# I2CRJ45X8.net
KiCad netlist of a schematic drawn in EAGLE
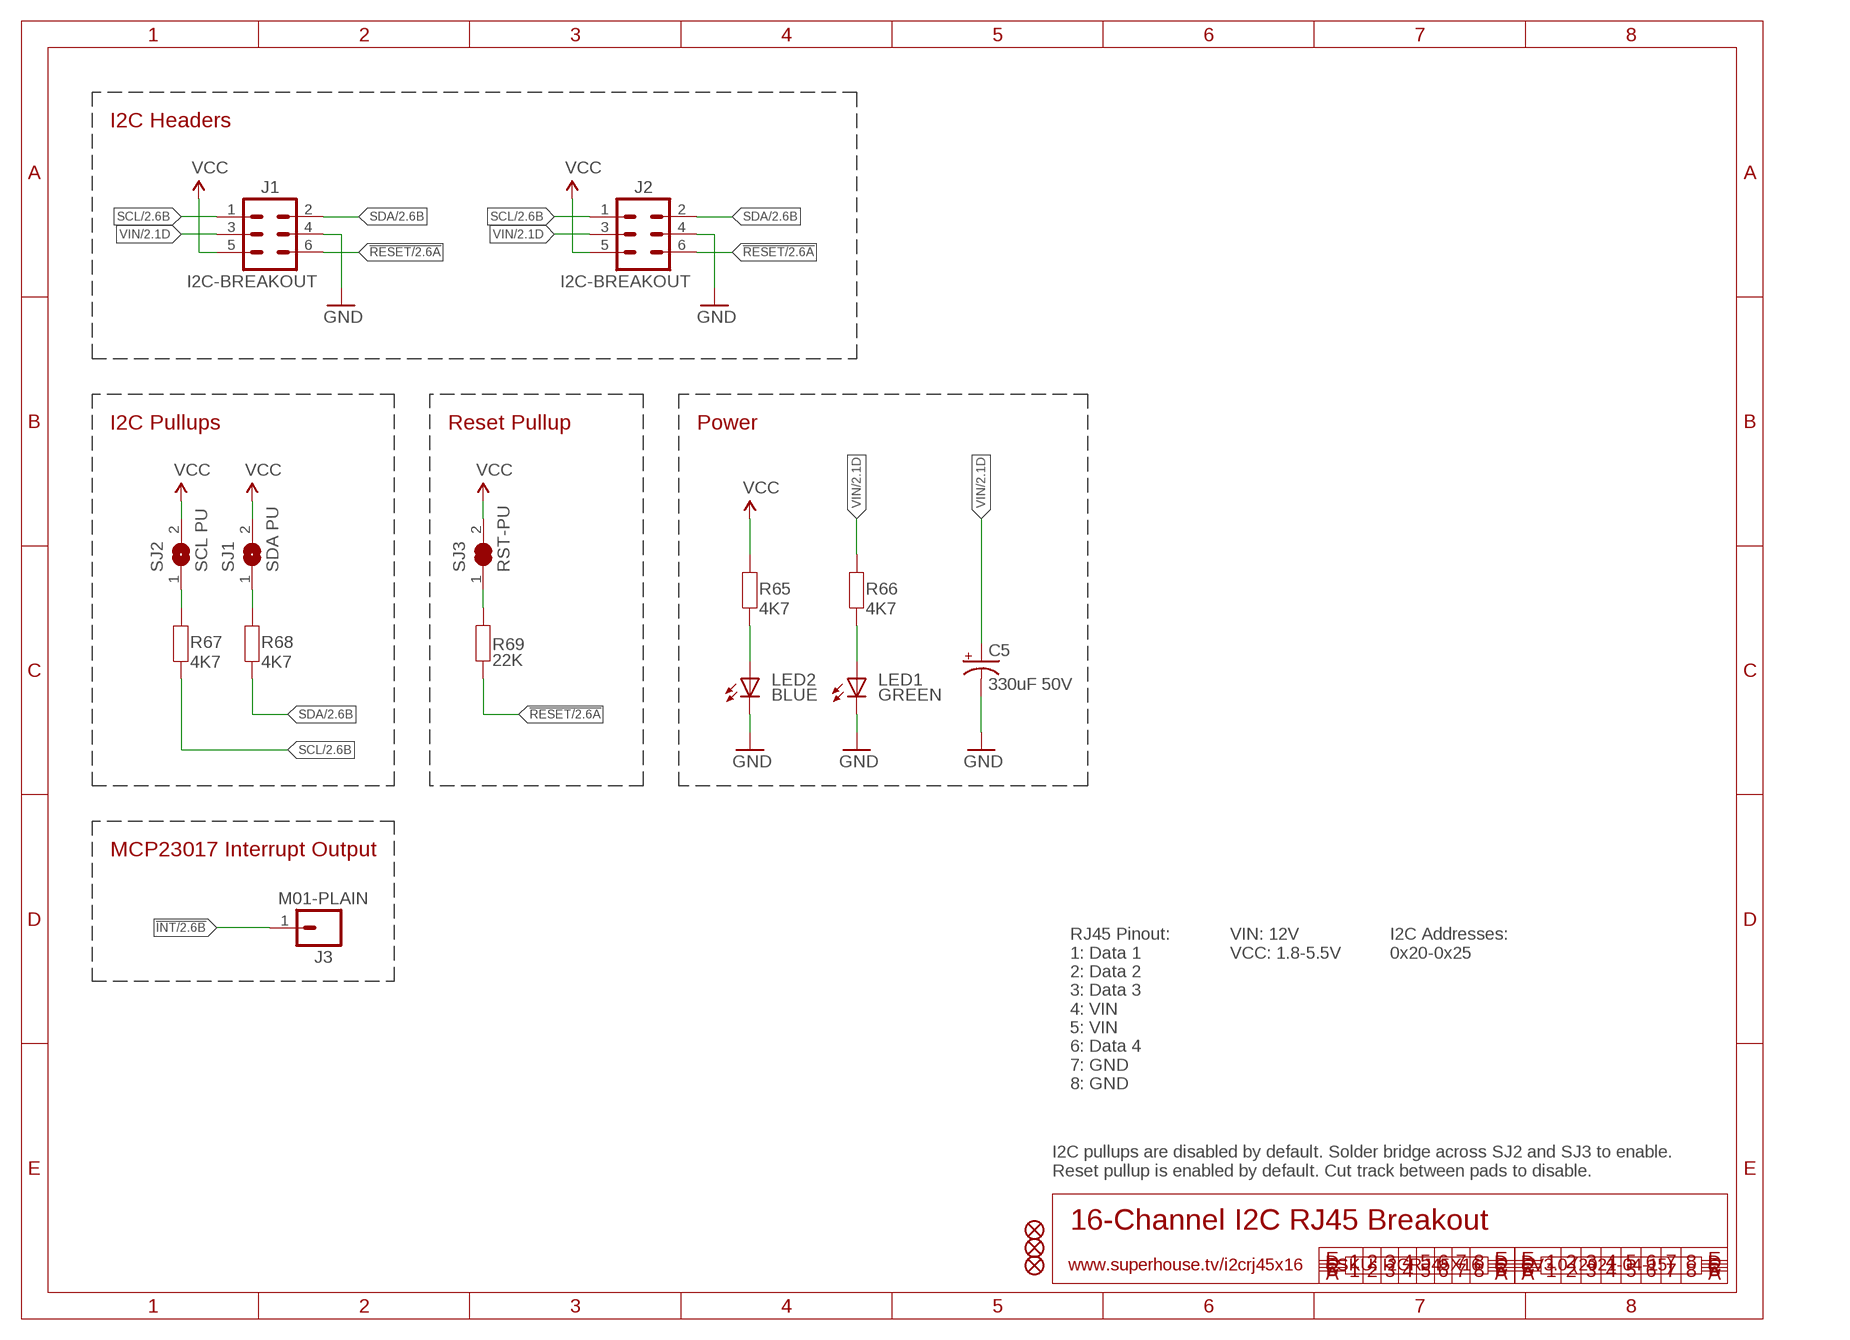
[diagram p0: schematic, sheet 1]
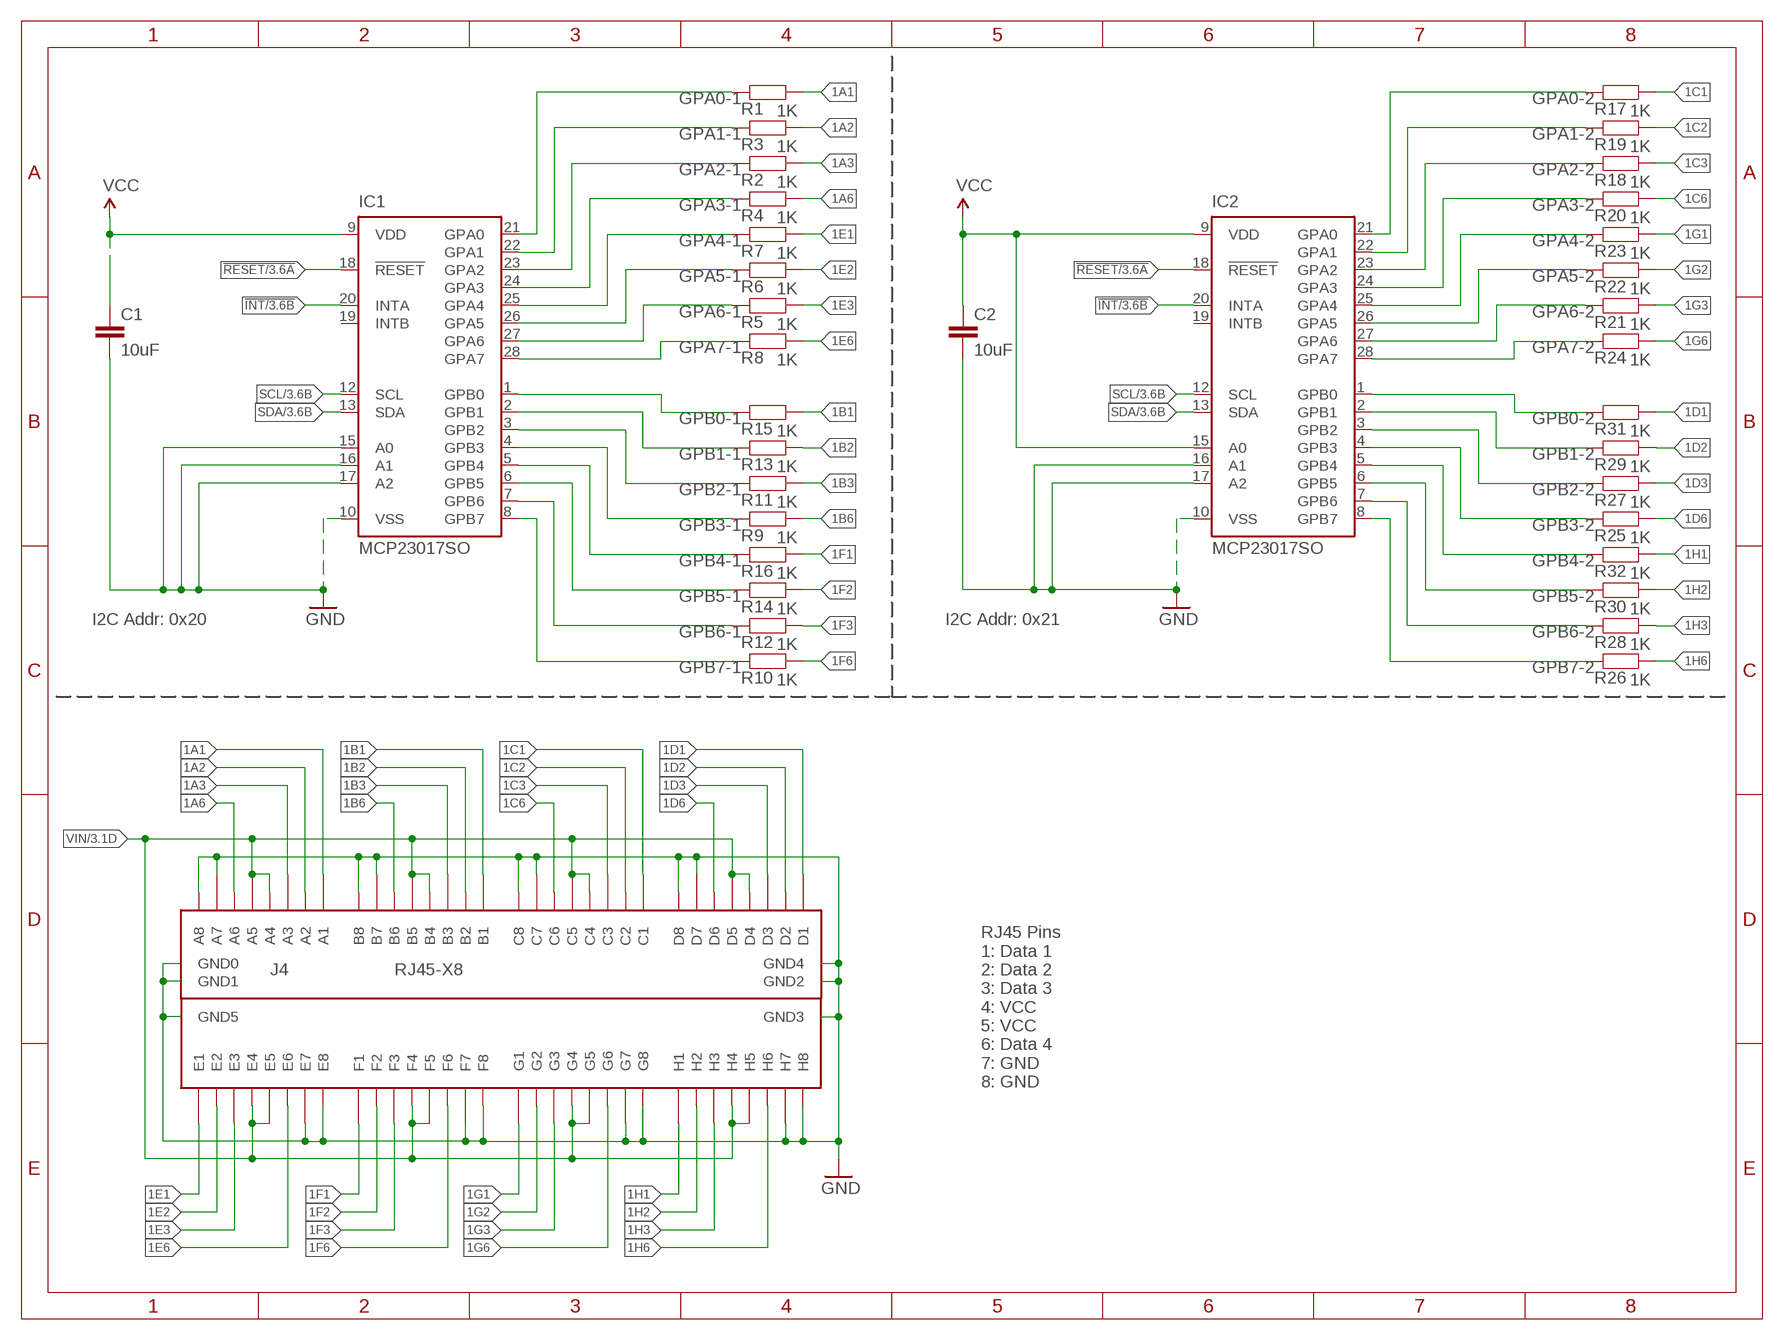
[diagram p1: schematic, sheet 2]
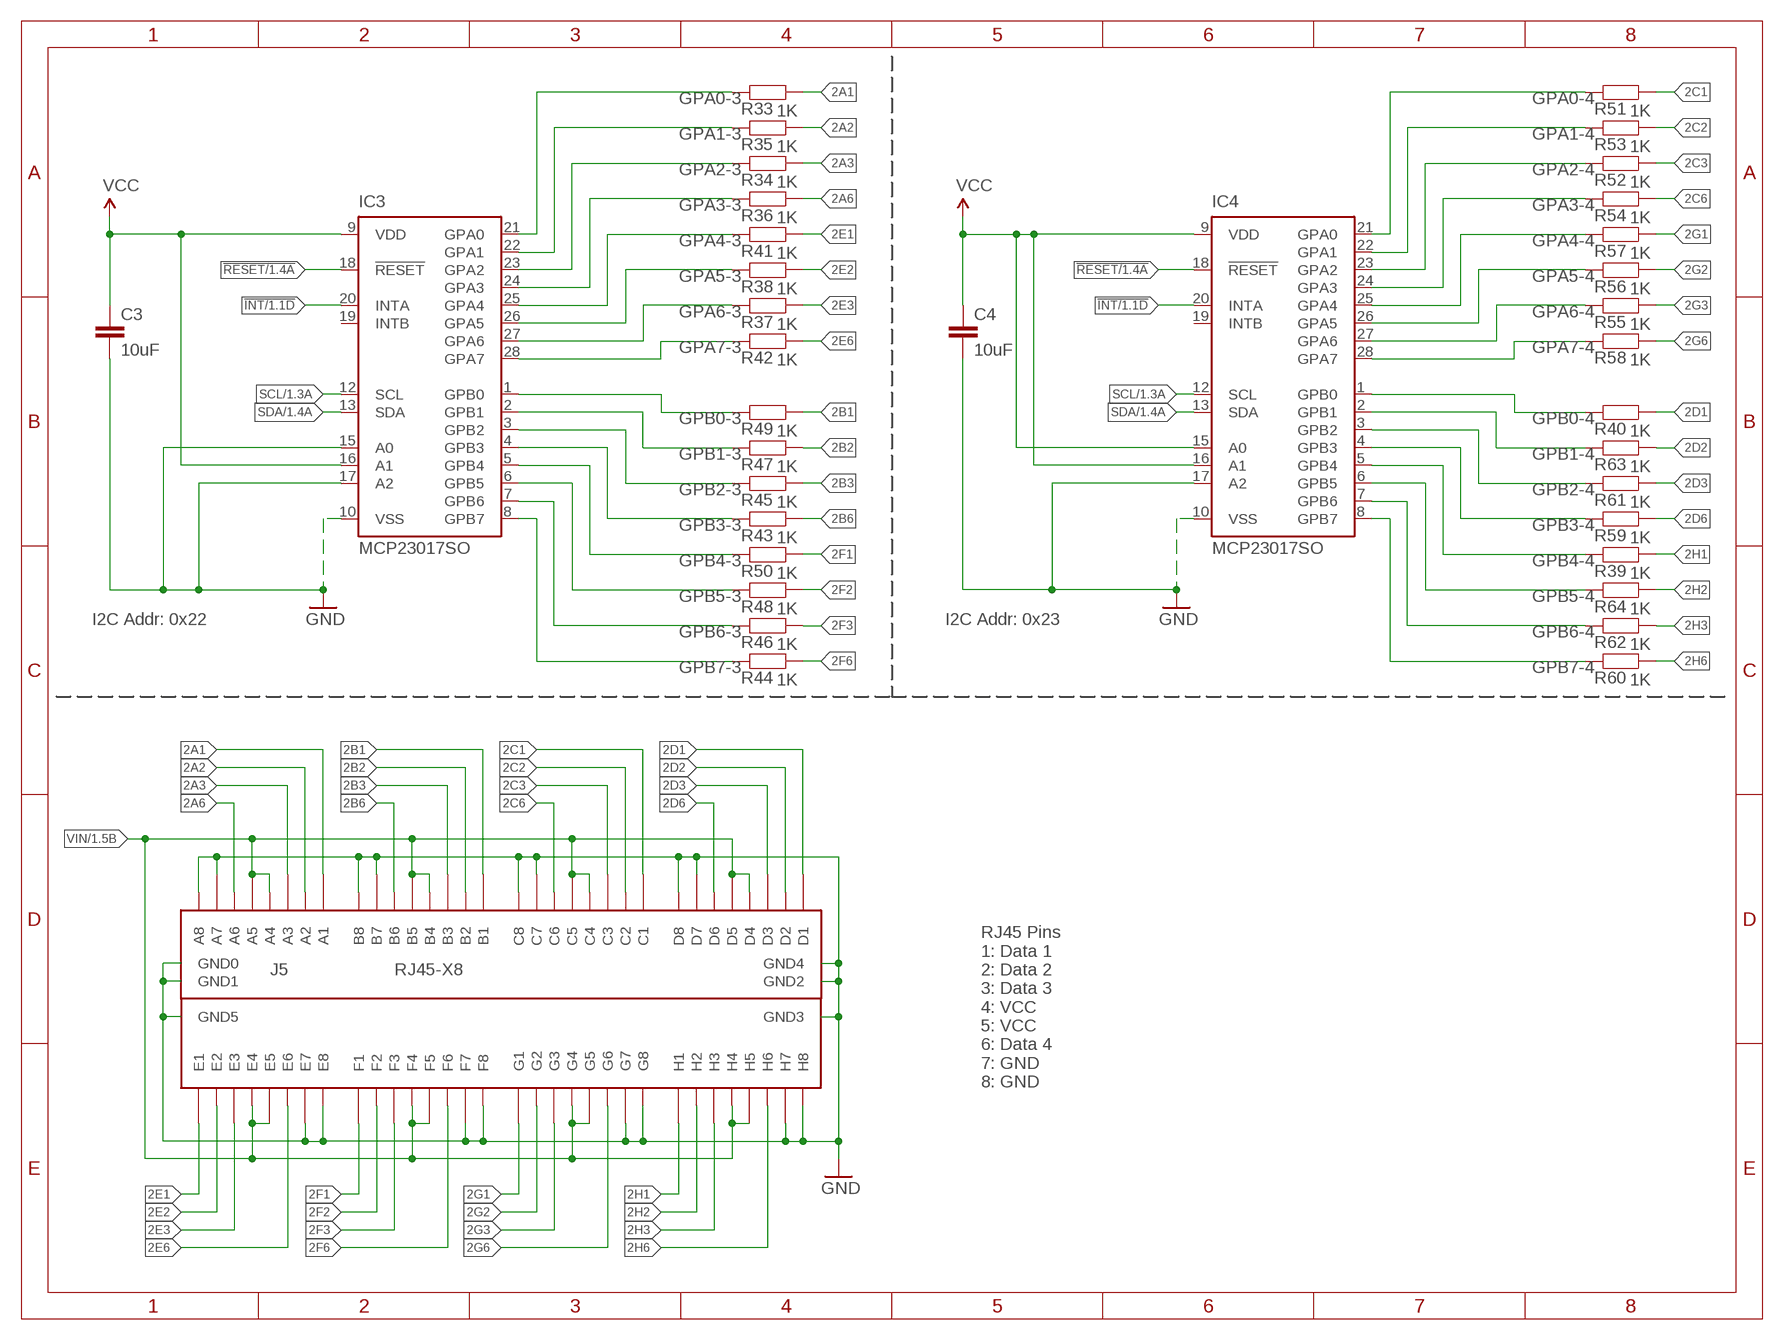
[diagram p2: schematic, sheet 3]

(export (version "E")
  (design (tool "Eeschema 10.0.6"))
  (components
    (comp (ref "C5")
      (value "330uF 50V")
      (footprint "eagle-import:PANASONIC_G")
      (libsource (lib "eagle-import") (part "CAP_POLG"))
    )
    (comp (ref "FID1")
      (value "FIDUCIAL1X2.5")
      (footprint "eagle-import:FIDUCIAL-1X2.5")
      (libsource (lib "eagle-import") (part "FIDUCIAL1X2.5"))
    )
    (comp (ref "FID2")
      (value "FIDUCIAL1X2.5")
      (footprint "eagle-import:FIDUCIAL-1X2.5")
      (libsource (lib "eagle-import") (part "FIDUCIAL1X2.5"))
    )
    (comp (ref "FID3")
      (value "FIDUCIAL1X2.5")
      (footprint "eagle-import:FIDUCIAL-1X2.5")
      (libsource (lib "eagle-import") (part "FIDUCIAL1X2.5"))
    )
    (comp (ref "J1")
      (value "I2C-BREAKOUT")
      (footprint "eagle-import:2X03-SHROUDED")
      (libsource (lib "eagle-import") (part "M02X3-SHROUDED"))
    )
    (comp (ref "J2")
      (value "I2C-BREAKOUT")
      (footprint "eagle-import:2X03-SHROUDED")
      (libsource (lib "eagle-import") (part "M02X3-SHROUDED"))
    )
    (comp (ref "J3")
      (value "M01-PLAIN")
      (footprint "eagle-import:1X01")
      (libsource (lib "eagle-import") (part "M01-PLAIN"))
    )
    (comp (ref "LED1")
      (value "GREEN")
      (footprint "eagle-import:LED-0603")
      (libsource (lib "eagle-import") (part "LED0603"))
    )
    (comp (ref "LED2")
      (value "BLUE")
      (footprint "eagle-import:LED-0603")
      (libsource (lib "eagle-import") (part "LED0603"))
    )
    (comp (ref "R65")
      (value "4K7")
      (footprint "eagle-import:R0603")
      (libsource (lib "eagle-import") (part "RESISTOR0603"))
    )
    (comp (ref "R66")
      (value "4K7")
      (footprint "eagle-import:R0603")
      (libsource (lib "eagle-import") (part "RESISTOR0603"))
    )
    (comp (ref "R67")
      (value "4K7")
      (footprint "eagle-import:R0603")
      (libsource (lib "eagle-import") (part "RESISTOR0603"))
    )
    (comp (ref "R68")
      (value "4K7")
      (footprint "eagle-import:R0603")
      (libsource (lib "eagle-import") (part "RESISTOR0603"))
    )
    (comp (ref "R69")
      (value "22K")
      (footprint "eagle-import:R0603")
      (libsource (lib "eagle-import") (part "RESISTOR0603"))
    )
    (comp (ref "SJ1")
      (value "SDA PU")
      (footprint "eagle-import:SJ")
      (libsource (lib "eagle-import") (part "SJ-NORMAL"))
    )
    (comp (ref "SJ2")
      (value "SCL PU")
      (footprint "eagle-import:SJ")
      (libsource (lib "eagle-import") (part "SJ-NORMAL"))
    )
    (comp (ref "SJ3")
      (value "RST-PU")
      (footprint "eagle-import:SJC")
      (libsource (lib "eagle-import") (part "SJC-NORMAL"))
    )
    (comp (ref "C1")
      (value "10uF")
      (footprint "eagle-import:C0805")
      (libsource (lib "eagle-import") (part "CAP0805"))
    )
    (comp (ref "C2")
      (value "10uF")
      (footprint "eagle-import:C0805")
      (libsource (lib "eagle-import") (part "CAP0805"))
    )
    (comp (ref "IC1")
      (value "MCP23017SO")
      (footprint "eagle-import:SO28W")
      (libsource (lib "eagle-import") (part "MCP23017SO"))
    )
    (comp (ref "IC2")
      (value "MCP23017SO")
      (footprint "eagle-import:SO28W")
      (libsource (lib "eagle-import") (part "MCP23017SO"))
    )
    (comp (ref "J4")
      (value "RJ45-X8")
      (footprint "eagle-import:RJ45-2X4")
      (libsource (lib "eagle-import") (part "RJ45-X8"))
    )
    (comp (ref "R1")
      (value "1K")
      (footprint "eagle-import:R0603")
      (libsource (lib "eagle-import") (part "RESISTOR0603"))
    )
    (comp (ref "R2")
      (value "1K")
      (footprint "eagle-import:R0603")
      (libsource (lib "eagle-import") (part "RESISTOR0603"))
    )
    (comp (ref "R3")
      (value "1K")
      (footprint "eagle-import:R0603")
      (libsource (lib "eagle-import") (part "RESISTOR0603"))
    )
    (comp (ref "R4")
      (value "1K")
      (footprint "eagle-import:R0603")
      (libsource (lib "eagle-import") (part "RESISTOR0603"))
    )
    (comp (ref "R5")
      (value "1K")
      (footprint "eagle-import:R0603")
      (libsource (lib "eagle-import") (part "RESISTOR0603"))
    )
    (comp (ref "R6")
      (value "1K")
      (footprint "eagle-import:R0603")
      (libsource (lib "eagle-import") (part "RESISTOR0603"))
    )
    (comp (ref "R7")
      (value "1K")
      (footprint "eagle-import:R0603")
      (libsource (lib "eagle-import") (part "RESISTOR0603"))
    )
    (comp (ref "R8")
      (value "1K")
      (footprint "eagle-import:R0603")
      (libsource (lib "eagle-import") (part "RESISTOR0603"))
    )
    (comp (ref "R9")
      (value "1K")
      (footprint "eagle-import:R0603")
      (libsource (lib "eagle-import") (part "RESISTOR0603"))
    )
    (comp (ref "R10")
      (value "1K")
      (footprint "eagle-import:R0603")
      (libsource (lib "eagle-import") (part "RESISTOR0603"))
    )
    (comp (ref "R11")
      (value "1K")
      (footprint "eagle-import:R0603")
      (libsource (lib "eagle-import") (part "RESISTOR0603"))
    )
    (comp (ref "R12")
      (value "1K")
      (footprint "eagle-import:R0603")
      (libsource (lib "eagle-import") (part "RESISTOR0603"))
    )
    (comp (ref "R13")
      (value "1K")
      (footprint "eagle-import:R0603")
      (libsource (lib "eagle-import") (part "RESISTOR0603"))
    )
    (comp (ref "R14")
      (value "1K")
      (footprint "eagle-import:R0603")
      (libsource (lib "eagle-import") (part "RESISTOR0603"))
    )
    (comp (ref "R15")
      (value "1K")
      (footprint "eagle-import:R0603")
      (libsource (lib "eagle-import") (part "RESISTOR0603"))
    )
    (comp (ref "R16")
      (value "1K")
      (footprint "eagle-import:R0603")
      (libsource (lib "eagle-import") (part "RESISTOR0603"))
    )
    (comp (ref "R17")
      (value "1K")
      (footprint "eagle-import:R0603")
      (libsource (lib "eagle-import") (part "RESISTOR0603"))
    )
    (comp (ref "R18")
      (value "1K")
      (footprint "eagle-import:R0603")
      (libsource (lib "eagle-import") (part "RESISTOR0603"))
    )
    (comp (ref "R19")
      (value "1K")
      (footprint "eagle-import:R0603")
      (libsource (lib "eagle-import") (part "RESISTOR0603"))
    )
    (comp (ref "R20")
      (value "1K")
      (footprint "eagle-import:R0603")
      (libsource (lib "eagle-import") (part "RESISTOR0603"))
    )
    (comp (ref "R21")
      (value "1K")
      (footprint "eagle-import:R0603")
      (libsource (lib "eagle-import") (part "RESISTOR0603"))
    )
    (comp (ref "R22")
      (value "1K")
      (footprint "eagle-import:R0603")
      (libsource (lib "eagle-import") (part "RESISTOR0603"))
    )
    (comp (ref "R23")
      (value "1K")
      (footprint "eagle-import:R0603")
      (libsource (lib "eagle-import") (part "RESISTOR0603"))
    )
    (comp (ref "R24")
      (value "1K")
      (footprint "eagle-import:R0603")
      (libsource (lib "eagle-import") (part "RESISTOR0603"))
    )
    (comp (ref "R25")
      (value "1K")
      (footprint "eagle-import:R0603")
      (libsource (lib "eagle-import") (part "RESISTOR0603"))
    )
    (comp (ref "R26")
      (value "1K")
      (footprint "eagle-import:R0603")
      (libsource (lib "eagle-import") (part "RESISTOR0603"))
    )
    (comp (ref "R27")
      (value "1K")
      (footprint "eagle-import:R0603")
      (libsource (lib "eagle-import") (part "RESISTOR0603"))
    )
    (comp (ref "R28")
      (value "1K")
      (footprint "eagle-import:R0603")
      (libsource (lib "eagle-import") (part "RESISTOR0603"))
    )
    (comp (ref "R29")
      (value "1K")
      (footprint "eagle-import:R0603")
      (libsource (lib "eagle-import") (part "RESISTOR0603"))
    )
    (comp (ref "R30")
      (value "1K")
      (footprint "eagle-import:R0603")
      (libsource (lib "eagle-import") (part "RESISTOR0603"))
    )
    (comp (ref "R31")
      (value "1K")
      (footprint "eagle-import:R0603")
      (libsource (lib "eagle-import") (part "RESISTOR0603"))
    )
    (comp (ref "R32")
      (value "1K")
      (footprint "eagle-import:R0603")
      (libsource (lib "eagle-import") (part "RESISTOR0603"))
    )
    (comp (ref "C3")
      (value "10uF")
      (footprint "eagle-import:C0805")
      (libsource (lib "eagle-import") (part "CAP0805"))
    )
    (comp (ref "C4")
      (value "10uF")
      (footprint "eagle-import:C0805")
      (libsource (lib "eagle-import") (part "CAP0805"))
    )
    (comp (ref "IC3")
      (value "MCP23017SO")
      (footprint "eagle-import:SO28W")
      (libsource (lib "eagle-import") (part "MCP23017SO"))
    )
    (comp (ref "IC4")
      (value "MCP23017SO")
      (footprint "eagle-import:SO28W")
      (libsource (lib "eagle-import") (part "MCP23017SO"))
    )
    (comp (ref "J5")
      (value "RJ45-X8")
      (footprint "eagle-import:RJ45-2X4")
      (libsource (lib "eagle-import") (part "RJ45-X8"))
    )
    (comp (ref "R33")
      (value "1K")
      (footprint "eagle-import:R0603")
      (libsource (lib "eagle-import") (part "RESISTOR0603"))
    )
    (comp (ref "R34")
      (value "1K")
      (footprint "eagle-import:R0603")
      (libsource (lib "eagle-import") (part "RESISTOR0603"))
    )
    (comp (ref "R35")
      (value "1K")
      (footprint "eagle-import:R0603")
      (libsource (lib "eagle-import") (part "RESISTOR0603"))
    )
    (comp (ref "R36")
      (value "1K")
      (footprint "eagle-import:R0603")
      (libsource (lib "eagle-import") (part "RESISTOR0603"))
    )
    (comp (ref "R37")
      (value "1K")
      (footprint "eagle-import:R0603")
      (libsource (lib "eagle-import") (part "RESISTOR0603"))
    )
    (comp (ref "R38")
      (value "1K")
      (footprint "eagle-import:R0603")
      (libsource (lib "eagle-import") (part "RESISTOR0603"))
    )
    (comp (ref "R39")
      (value "1K")
      (footprint "eagle-import:R0603")
      (libsource (lib "eagle-import") (part "RESISTOR0603"))
    )
    (comp (ref "R40")
      (value "1K")
      (footprint "eagle-import:R0603")
      (libsource (lib "eagle-import") (part "RESISTOR0603"))
    )
    (comp (ref "R41")
      (value "1K")
      (footprint "eagle-import:R0603")
      (libsource (lib "eagle-import") (part "RESISTOR0603"))
    )
    (comp (ref "R42")
      (value "1K")
      (footprint "eagle-import:R0603")
      (libsource (lib "eagle-import") (part "RESISTOR0603"))
    )
    (comp (ref "R43")
      (value "1K")
      (footprint "eagle-import:R0603")
      (libsource (lib "eagle-import") (part "RESISTOR0603"))
    )
    (comp (ref "R44")
      (value "1K")
      (footprint "eagle-import:R0603")
      (libsource (lib "eagle-import") (part "RESISTOR0603"))
    )
    (comp (ref "R45")
      (value "1K")
      (footprint "eagle-import:R0603")
      (libsource (lib "eagle-import") (part "RESISTOR0603"))
    )
    (comp (ref "R46")
      (value "1K")
      (footprint "eagle-import:R0603")
      (libsource (lib "eagle-import") (part "RESISTOR0603"))
    )
    (comp (ref "R47")
      (value "1K")
      (footprint "eagle-import:R0603")
      (libsource (lib "eagle-import") (part "RESISTOR0603"))
    )
    (comp (ref "R48")
      (value "1K")
      (footprint "eagle-import:R0603")
      (libsource (lib "eagle-import") (part "RESISTOR0603"))
    )
    (comp (ref "R49")
      (value "1K")
      (footprint "eagle-import:R0603")
      (libsource (lib "eagle-import") (part "RESISTOR0603"))
    )
    (comp (ref "R50")
      (value "1K")
      (footprint "eagle-import:R0603")
      (libsource (lib "eagle-import") (part "RESISTOR0603"))
    )
    (comp (ref "R51")
      (value "1K")
      (footprint "eagle-import:R0603")
      (libsource (lib "eagle-import") (part "RESISTOR0603"))
    )
    (comp (ref "R52")
      (value "1K")
      (footprint "eagle-import:R0603")
      (libsource (lib "eagle-import") (part "RESISTOR0603"))
    )
    (comp (ref "R53")
      (value "1K")
      (footprint "eagle-import:R0603")
      (libsource (lib "eagle-import") (part "RESISTOR0603"))
    )
    (comp (ref "R54")
      (value "1K")
      (footprint "eagle-import:R0603")
      (libsource (lib "eagle-import") (part "RESISTOR0603"))
    )
    (comp (ref "R55")
      (value "1K")
      (footprint "eagle-import:R0603")
      (libsource (lib "eagle-import") (part "RESISTOR0603"))
    )
    (comp (ref "R56")
      (value "1K")
      (footprint "eagle-import:R0603")
      (libsource (lib "eagle-import") (part "RESISTOR0603"))
    )
    (comp (ref "R57")
      (value "1K")
      (footprint "eagle-import:R0603")
      (libsource (lib "eagle-import") (part "RESISTOR0603"))
    )
    (comp (ref "R58")
      (value "1K")
      (footprint "eagle-import:R0603")
      (libsource (lib "eagle-import") (part "RESISTOR0603"))
    )
    (comp (ref "R59")
      (value "1K")
      (footprint "eagle-import:R0603")
      (libsource (lib "eagle-import") (part "RESISTOR0603"))
    )
    (comp (ref "R60")
      (value "1K")
      (footprint "eagle-import:R0603")
      (libsource (lib "eagle-import") (part "RESISTOR0603"))
    )
    (comp (ref "R61")
      (value "1K")
      (footprint "eagle-import:R0603")
      (libsource (lib "eagle-import") (part "RESISTOR0603"))
    )
    (comp (ref "R62")
      (value "1K")
      (footprint "eagle-import:R0603")
      (libsource (lib "eagle-import") (part "RESISTOR0603"))
    )
    (comp (ref "R63")
      (value "1K")
      (footprint "eagle-import:R0603")
      (libsource (lib "eagle-import") (part "RESISTOR0603"))
    )
    (comp (ref "R64")
      (value "1K")
      (footprint "eagle-import:R0603")
      (libsource (lib "eagle-import") (part "RESISTOR0603"))
    )
  )
  (nets
    (net (code "1") (name "1A1") (class "Default")
      (node (ref "J4") (pin "A1") (pinfunction "A1_A1") (pintype "bidirectional"))
      (node (ref "R1") (pin "2") (pinfunction "2_2") (pintype "passive"))
    )
    (net (code "2") (name "1A2") (class "Default")
      (node (ref "J4") (pin "A2") (pinfunction "A2_A2") (pintype "bidirectional"))
      (node (ref "R3") (pin "2") (pinfunction "2_2") (pintype "passive"))
    )
    (net (code "3") (name "1A3") (class "Default")
      (node (ref "J4") (pin "A3") (pinfunction "A3_A3") (pintype "bidirectional"))
      (node (ref "R2") (pin "2") (pinfunction "2_2") (pintype "passive"))
    )
    (net (code "4") (name "1A6") (class "Default")
      (node (ref "J4") (pin "A6") (pinfunction "A6_A6") (pintype "bidirectional"))
      (node (ref "R4") (pin "2") (pinfunction "2_2") (pintype "passive"))
    )
    (net (code "5") (name "1B1") (class "Default")
      (node (ref "J4") (pin "B1") (pinfunction "B1_B1") (pintype "bidirectional"))
      (node (ref "R15") (pin "2") (pinfunction "2_2") (pintype "passive"))
    )
    (net (code "6") (name "1B2") (class "Default")
      (node (ref "J4") (pin "B2") (pinfunction "B2_B2") (pintype "bidirectional"))
      (node (ref "R13") (pin "2") (pinfunction "2_2") (pintype "passive"))
    )
    (net (code "7") (name "1B3") (class "Default")
      (node (ref "J4") (pin "B3") (pinfunction "B3_B3") (pintype "bidirectional"))
      (node (ref "R11") (pin "2") (pinfunction "2_2") (pintype "passive"))
    )
    (net (code "8") (name "1B6") (class "Default")
      (node (ref "J4") (pin "B6") (pinfunction "B6_B6") (pintype "bidirectional"))
      (node (ref "R9") (pin "2") (pinfunction "2_2") (pintype "passive"))
    )
    (net (code "9") (name "1C1") (class "Default")
      (node (ref "J4") (pin "C1") (pinfunction "C1_C1") (pintype "bidirectional"))
      (node (ref "R17") (pin "2") (pinfunction "2_2") (pintype "passive"))
    )
    (net (code "10") (name "1C2") (class "Default")
      (node (ref "J4") (pin "C2") (pinfunction "C2_C2") (pintype "bidirectional"))
      (node (ref "R19") (pin "2") (pinfunction "2_2") (pintype "passive"))
    )
    (net (code "11") (name "1C3") (class "Default")
      (node (ref "J4") (pin "C3") (pinfunction "C3_C3") (pintype "bidirectional"))
      (node (ref "R18") (pin "2") (pinfunction "2_2") (pintype "passive"))
    )
    (net (code "12") (name "1C6") (class "Default")
      (node (ref "J4") (pin "C6") (pinfunction "C6_C6") (pintype "bidirectional"))
      (node (ref "R20") (pin "2") (pinfunction "2_2") (pintype "passive"))
    )
    (net (code "13") (name "1D1") (class "Default")
      (node (ref "J4") (pin "D1") (pinfunction "D1_D1") (pintype "bidirectional"))
      (node (ref "R31") (pin "2") (pinfunction "2_2") (pintype "passive"))
    )
    (net (code "14") (name "1D2") (class "Default")
      (node (ref "J4") (pin "D2") (pinfunction "D2_D2") (pintype "bidirectional"))
      (node (ref "R29") (pin "2") (pinfunction "2_2") (pintype "passive"))
    )
    (net (code "15") (name "1D3") (class "Default")
      (node (ref "J4") (pin "D3") (pinfunction "D3_D3") (pintype "bidirectional"))
      (node (ref "R27") (pin "2") (pinfunction "2_2") (pintype "passive"))
    )
    (net (code "16") (name "1D6") (class "Default")
      (node (ref "J4") (pin "D6") (pinfunction "D6_D6") (pintype "bidirectional"))
      (node (ref "R25") (pin "2") (pinfunction "2_2") (pintype "passive"))
    )
    (net (code "17") (name "1E1") (class "Default")
      (node (ref "J4") (pin "E1") (pinfunction "E1_E1") (pintype "bidirectional"))
      (node (ref "R7") (pin "2") (pinfunction "2_2") (pintype "passive"))
    )
    (net (code "18") (name "1E2") (class "Default")
      (node (ref "J4") (pin "E2") (pinfunction "E2_E2") (pintype "bidirectional"))
      (node (ref "R6") (pin "2") (pinfunction "2_2") (pintype "passive"))
    )
    (net (code "19") (name "1E3") (class "Default")
      (node (ref "J4") (pin "E3") (pinfunction "E3_E3") (pintype "bidirectional"))
      (node (ref "R5") (pin "2") (pinfunction "2_2") (pintype "passive"))
    )
    (net (code "20") (name "1E6") (class "Default")
      (node (ref "J4") (pin "E6") (pinfunction "E6_E6") (pintype "bidirectional"))
      (node (ref "R8") (pin "2") (pinfunction "2_2") (pintype "passive"))
    )
    (net (code "21") (name "1F1") (class "Default")
      (node (ref "J4") (pin "F1") (pinfunction "F1_F1") (pintype "bidirectional"))
      (node (ref "R16") (pin "2") (pinfunction "2_2") (pintype "passive"))
    )
    (net (code "22") (name "1F2") (class "Default")
      (node (ref "J4") (pin "F2") (pinfunction "F2_F2") (pintype "bidirectional"))
      (node (ref "R14") (pin "2") (pinfunction "2_2") (pintype "passive"))
    )
    (net (code "23") (name "1F3") (class "Default")
      (node (ref "J4") (pin "F3") (pinfunction "F3_F3") (pintype "bidirectional"))
      (node (ref "R12") (pin "2") (pinfunction "2_2") (pintype "passive"))
    )
    (net (code "24") (name "1F6") (class "Default")
      (node (ref "J4") (pin "F6") (pinfunction "F6_F6") (pintype "bidirectional"))
      (node (ref "R10") (pin "2") (pinfunction "2_2") (pintype "passive"))
    )
    (net (code "25") (name "1G1") (class "Default")
      (node (ref "J4") (pin "G1") (pinfunction "G1_G1") (pintype "bidirectional"))
      (node (ref "R23") (pin "2") (pinfunction "2_2") (pintype "passive"))
    )
    (net (code "26") (name "1G2") (class "Default")
      (node (ref "J4") (pin "G2") (pinfunction "G2_G2") (pintype "bidirectional"))
      (node (ref "R22") (pin "2") (pinfunction "2_2") (pintype "passive"))
    )
    (net (code "27") (name "1G3") (class "Default")
      (node (ref "J4") (pin "G3") (pinfunction "G3_G3") (pintype "bidirectional"))
      (node (ref "R21") (pin "2") (pinfunction "2_2") (pintype "passive"))
    )
    (net (code "28") (name "1G6") (class "Default")
      (node (ref "J4") (pin "G6") (pinfunction "G6_G6") (pintype "bidirectional"))
      (node (ref "R24") (pin "2") (pinfunction "2_2") (pintype "passive"))
    )
    (net (code "29") (name "1H1") (class "Default")
      (node (ref "J4") (pin "H1") (pinfunction "H1_H1") (pintype "bidirectional"))
      (node (ref "R32") (pin "2") (pinfunction "2_2") (pintype "passive"))
    )
    (net (code "30") (name "1H2") (class "Default")
      (node (ref "J4") (pin "H2") (pinfunction "H2_H2") (pintype "bidirectional"))
      (node (ref "R30") (pin "2") (pinfunction "2_2") (pintype "passive"))
    )
    (net (code "31") (name "1H3") (class "Default")
      (node (ref "J4") (pin "H3") (pinfunction "H3_H3") (pintype "bidirectional"))
      (node (ref "R28") (pin "2") (pinfunction "2_2") (pintype "passive"))
    )
    (net (code "32") (name "1H6") (class "Default")
      (node (ref "J4") (pin "H6") (pinfunction "H6_H6") (pintype "bidirectional"))
      (node (ref "R26") (pin "2") (pinfunction "2_2") (pintype "passive"))
    )
    (net (code "33") (name "2A1") (class "Default")
      (node (ref "J5") (pin "A1") (pinfunction "A1_A1") (pintype "bidirectional"))
      (node (ref "R33") (pin "2") (pinfunction "2_2") (pintype "passive"))
    )
    (net (code "34") (name "2A2") (class "Default")
      (node (ref "J5") (pin "A2") (pinfunction "A2_A2") (pintype "bidirectional"))
      (node (ref "R35") (pin "2") (pinfunction "2_2") (pintype "passive"))
    )
    (net (code "35") (name "2A3") (class "Default")
      (node (ref "J5") (pin "A3") (pinfunction "A3_A3") (pintype "bidirectional"))
      (node (ref "R34") (pin "2") (pinfunction "2_2") (pintype "passive"))
    )
    (net (code "36") (name "2A6") (class "Default")
      (node (ref "J5") (pin "A6") (pinfunction "A6_A6") (pintype "bidirectional"))
      (node (ref "R36") (pin "2") (pinfunction "2_2") (pintype "passive"))
    )
    (net (code "37") (name "2B1") (class "Default")
      (node (ref "J5") (pin "B1") (pinfunction "B1_B1") (pintype "bidirectional"))
      (node (ref "R49") (pin "2") (pinfunction "2_2") (pintype "passive"))
    )
    (net (code "38") (name "2B2") (class "Default")
      (node (ref "J5") (pin "B2") (pinfunction "B2_B2") (pintype "bidirectional"))
      (node (ref "R47") (pin "2") (pinfunction "2_2") (pintype "passive"))
    )
    (net (code "39") (name "2B3") (class "Default")
      (node (ref "J5") (pin "B3") (pinfunction "B3_B3") (pintype "bidirectional"))
      (node (ref "R45") (pin "2") (pinfunction "2_2") (pintype "passive"))
    )
    (net (code "40") (name "2B6") (class "Default")
      (node (ref "J5") (pin "B6") (pinfunction "B6_B6") (pintype "bidirectional"))
      (node (ref "R43") (pin "2") (pinfunction "2_2") (pintype "passive"))
    )
    (net (code "41") (name "2C1") (class "Default")
      (node (ref "J5") (pin "C1") (pinfunction "C1_C1") (pintype "bidirectional"))
      (node (ref "R51") (pin "2") (pinfunction "2_2") (pintype "passive"))
    )
    (net (code "42") (name "2C2") (class "Default")
      (node (ref "J5") (pin "C2") (pinfunction "C2_C2") (pintype "bidirectional"))
      (node (ref "R53") (pin "2") (pinfunction "2_2") (pintype "passive"))
    )
    (net (code "43") (name "2C3") (class "Default")
      (node (ref "J5") (pin "C3") (pinfunction "C3_C3") (pintype "bidirectional"))
      (node (ref "R52") (pin "2") (pinfunction "2_2") (pintype "passive"))
    )
    (net (code "44") (name "2C6") (class "Default")
      (node (ref "J5") (pin "C6") (pinfunction "C6_C6") (pintype "bidirectional"))
      (node (ref "R54") (pin "2") (pinfunction "2_2") (pintype "passive"))
    )
    (net (code "45") (name "2D1") (class "Default")
      (node (ref "J5") (pin "D1") (pinfunction "D1_D1") (pintype "bidirectional"))
      (node (ref "R40") (pin "2") (pinfunction "2_2") (pintype "passive"))
    )
    (net (code "46") (name "2D2") (class "Default")
      (node (ref "J5") (pin "D2") (pinfunction "D2_D2") (pintype "bidirectional"))
      (node (ref "R63") (pin "2") (pinfunction "2_2") (pintype "passive"))
    )
    (net (code "47") (name "2D3") (class "Default")
      (node (ref "J5") (pin "D3") (pinfunction "D3_D3") (pintype "bidirectional"))
      (node (ref "R61") (pin "2") (pinfunction "2_2") (pintype "passive"))
    )
    (net (code "48") (name "2D6") (class "Default")
      (node (ref "J5") (pin "D6") (pinfunction "D6_D6") (pintype "bidirectional"))
      (node (ref "R59") (pin "2") (pinfunction "2_2") (pintype "passive"))
    )
    (net (code "49") (name "2E1") (class "Default")
      (node (ref "J5") (pin "E1") (pinfunction "E1_E1") (pintype "bidirectional"))
      (node (ref "R41") (pin "2") (pinfunction "2_2") (pintype "passive"))
    )
    (net (code "50") (name "2E2") (class "Default")
      (node (ref "J5") (pin "E2") (pinfunction "E2_E2") (pintype "bidirectional"))
      (node (ref "R38") (pin "2") (pinfunction "2_2") (pintype "passive"))
    )
    (net (code "51") (name "2E3") (class "Default")
      (node (ref "J5") (pin "E3") (pinfunction "E3_E3") (pintype "bidirectional"))
      (node (ref "R37") (pin "2") (pinfunction "2_2") (pintype "passive"))
    )
    (net (code "52") (name "2E6") (class "Default")
      (node (ref "J5") (pin "E6") (pinfunction "E6_E6") (pintype "bidirectional"))
      (node (ref "R42") (pin "2") (pinfunction "2_2") (pintype "passive"))
    )
    (net (code "53") (name "2F1") (class "Default")
      (node (ref "J5") (pin "F1") (pinfunction "F1_F1") (pintype "bidirectional"))
      (node (ref "R50") (pin "2") (pinfunction "2_2") (pintype "passive"))
    )
    (net (code "54") (name "2F2") (class "Default")
      (node (ref "J5") (pin "F2") (pinfunction "F2_F2") (pintype "bidirectional"))
      (node (ref "R48") (pin "2") (pinfunction "2_2") (pintype "passive"))
    )
    (net (code "55") (name "2F3") (class "Default")
      (node (ref "J5") (pin "F3") (pinfunction "F3_F3") (pintype "bidirectional"))
      (node (ref "R46") (pin "2") (pinfunction "2_2") (pintype "passive"))
    )
    (net (code "56") (name "2F6") (class "Default")
      (node (ref "J5") (pin "F6") (pinfunction "F6_F6") (pintype "bidirectional"))
      (node (ref "R44") (pin "2") (pinfunction "2_2") (pintype "passive"))
    )
    (net (code "57") (name "2G1") (class "Default")
      (node (ref "J5") (pin "G1") (pinfunction "G1_G1") (pintype "bidirectional"))
      (node (ref "R57") (pin "2") (pinfunction "2_2") (pintype "passive"))
    )
    (net (code "58") (name "2G2") (class "Default")
      (node (ref "J5") (pin "G2") (pinfunction "G2_G2") (pintype "bidirectional"))
      (node (ref "R56") (pin "2") (pinfunction "2_2") (pintype "passive"))
    )
    (net (code "59") (name "2G3") (class "Default")
      (node (ref "J5") (pin "G3") (pinfunction "G3_G3") (pintype "bidirectional"))
      (node (ref "R55") (pin "2") (pinfunction "2_2") (pintype "passive"))
    )
    (net (code "60") (name "2G6") (class "Default")
      (node (ref "J5") (pin "G6") (pinfunction "G6_G6") (pintype "bidirectional"))
      (node (ref "R58") (pin "2") (pinfunction "2_2") (pintype "passive"))
    )
    (net (code "61") (name "2H1") (class "Default")
      (node (ref "J5") (pin "H1") (pinfunction "H1_H1") (pintype "bidirectional"))
      (node (ref "R39") (pin "2") (pinfunction "2_2") (pintype "passive"))
    )
    (net (code "62") (name "2H2") (class "Default")
      (node (ref "J5") (pin "H2") (pinfunction "H2_H2") (pintype "bidirectional"))
      (node (ref "R64") (pin "2") (pinfunction "2_2") (pintype "passive"))
    )
    (net (code "63") (name "2H3") (class "Default")
      (node (ref "J5") (pin "H3") (pinfunction "H3_H3") (pintype "bidirectional"))
      (node (ref "R62") (pin "2") (pinfunction "2_2") (pintype "passive"))
    )
    (net (code "64") (name "2H6") (class "Default")
      (node (ref "J5") (pin "H6") (pinfunction "H6_H6") (pintype "bidirectional"))
      (node (ref "R60") (pin "2") (pinfunction "2_2") (pintype "passive"))
    )
    (net (code "65") (name "GND") (class "Default")
      (node (ref "C1") (pin "2") (pinfunction "2_2") (pintype "passive"))
      (node (ref "C2") (pin "2") (pinfunction "2_2") (pintype "passive"))
      (node (ref "C3") (pin "2") (pinfunction "2_2") (pintype "passive"))
      (node (ref "C4") (pin "2") (pinfunction "2_2") (pintype "passive"))
      (node (ref "C5") (pin "-") (pinfunction "-_-") (pintype "passive"))
      (node (ref "IC1") (pin "10") (pinfunction "VSS_10") (pintype "power_in"))
      (node (ref "IC1") (pin "15") (pinfunction "A0_15") (pintype "input"))
      (node (ref "IC1") (pin "16") (pinfunction "A1_16") (pintype "input"))
      (node (ref "IC1") (pin "17") (pinfunction "A2_17") (pintype "input"))
      (node (ref "IC2") (pin "10") (pinfunction "VSS_10") (pintype "power_in"))
      (node (ref "IC2") (pin "16") (pinfunction "A1_16") (pintype "input"))
      (node (ref "IC2") (pin "17") (pinfunction "A2_17") (pintype "input"))
      (node (ref "IC3") (pin "10") (pinfunction "VSS_10") (pintype "power_in"))
      (node (ref "IC3") (pin "15") (pinfunction "A0_15") (pintype "input"))
      (node (ref "IC3") (pin "17") (pinfunction "A2_17") (pintype "input"))
      (node (ref "IC4") (pin "10") (pinfunction "VSS_10") (pintype "power_in"))
      (node (ref "IC4") (pin "17") (pinfunction "A2_17") (pintype "input"))
      (node (ref "J1") (pin "4") (pinfunction "4_4") (pintype "passive"))
      (node (ref "J2") (pin "4") (pinfunction "4_4") (pintype "passive"))
      (node (ref "J4") (pin "A7") (pinfunction "A7_A7") (pintype "bidirectional"))
      (node (ref "J4") (pin "A8") (pinfunction "A8_A8") (pintype "bidirectional"))
      (node (ref "J4") (pin "B7") (pinfunction "B7_B7") (pintype "bidirectional"))
      (node (ref "J4") (pin "B8") (pinfunction "B8_B8") (pintype "bidirectional"))
      (node (ref "J4") (pin "C7") (pinfunction "C7_C7") (pintype "bidirectional"))
      (node (ref "J4") (pin "C8") (pinfunction "C8_C8") (pintype "bidirectional"))
      (node (ref "J4") (pin "D7") (pinfunction "D7_D7") (pintype "bidirectional"))
      (node (ref "J4") (pin "D8") (pinfunction "D8_D8") (pintype "bidirectional"))
      (node (ref "J4") (pin "E7") (pinfunction "E7_E7") (pintype "bidirectional"))
      (node (ref "J4") (pin "E8") (pinfunction "E8_E8") (pintype "bidirectional"))
      (node (ref "J4") (pin "F7") (pinfunction "F7_F7") (pintype "bidirectional"))
      (node (ref "J4") (pin "F8") (pinfunction "F8_F8") (pintype "bidirectional"))
      (node (ref "J4") (pin "G7") (pinfunction "G7_G7") (pintype "bidirectional"))
      (node (ref "J4") (pin "G8") (pinfunction "G8_G8") (pintype "bidirectional"))
      (node (ref "J4") (pin "GND0") (pinfunction "GND0_GND0") (pintype "power_in"))
      (node (ref "J4") (pin "GND1") (pinfunction "GND1_GND1") (pintype "power_in"))
      (node (ref "J4") (pin "GND2") (pinfunction "GND2_GND2") (pintype "power_in"))
      (node (ref "J4") (pin "GND3") (pinfunction "GND3_GND3") (pintype "power_in"))
      (node (ref "J4") (pin "GND4") (pinfunction "GND4_GND4") (pintype "power_in"))
      (node (ref "J4") (pin "GND5") (pinfunction "GND5_GND5") (pintype "power_in"))
      (node (ref "J4") (pin "H7") (pinfunction "H7_H7") (pintype "bidirectional"))
      (node (ref "J4") (pin "H8") (pinfunction "H8_H8") (pintype "bidirectional"))
      (node (ref "J5") (pin "A7") (pinfunction "A7_A7") (pintype "bidirectional"))
      (node (ref "J5") (pin "A8") (pinfunction "A8_A8") (pintype "bidirectional"))
      (node (ref "J5") (pin "B7") (pinfunction "B7_B7") (pintype "bidirectional"))
      (node (ref "J5") (pin "B8") (pinfunction "B8_B8") (pintype "bidirectional"))
      (node (ref "J5") (pin "C7") (pinfunction "C7_C7") (pintype "bidirectional"))
      (node (ref "J5") (pin "C8") (pinfunction "C8_C8") (pintype "bidirectional"))
      (node (ref "J5") (pin "D7") (pinfunction "D7_D7") (pintype "bidirectional"))
      (node (ref "J5") (pin "D8") (pinfunction "D8_D8") (pintype "bidirectional"))
      (node (ref "J5") (pin "E7") (pinfunction "E7_E7") (pintype "bidirectional"))
      (node (ref "J5") (pin "E8") (pinfunction "E8_E8") (pintype "bidirectional"))
      (node (ref "J5") (pin "F7") (pinfunction "F7_F7") (pintype "bidirectional"))
      (node (ref "J5") (pin "F8") (pinfunction "F8_F8") (pintype "bidirectional"))
      (node (ref "J5") (pin "G7") (pinfunction "G7_G7") (pintype "bidirectional"))
      (node (ref "J5") (pin "G8") (pinfunction "G8_G8") (pintype "bidirectional"))
      (node (ref "J5") (pin "GND0") (pinfunction "GND0_GND0") (pintype "power_in"))
      (node (ref "J5") (pin "GND1") (pinfunction "GND1_GND1") (pintype "power_in"))
      (node (ref "J5") (pin "GND2") (pinfunction "GND2_GND2") (pintype "power_in"))
      (node (ref "J5") (pin "GND3") (pinfunction "GND3_GND3") (pintype "power_in"))
      (node (ref "J5") (pin "GND4") (pinfunction "GND4_GND4") (pintype "power_in"))
      (node (ref "J5") (pin "GND5") (pinfunction "GND5_GND5") (pintype "power_in"))
      (node (ref "J5") (pin "H7") (pinfunction "H7_H7") (pintype "bidirectional"))
      (node (ref "J5") (pin "H8") (pinfunction "H8_H8") (pintype "bidirectional"))
      (node (ref "LED1") (pin "C") (pinfunction "C_C") (pintype "passive"))
      (node (ref "LED2") (pin "C") (pinfunction "C_C") (pintype "passive"))
    )
    (net (code "66") (name "GPA0-1") (class "Default")
      (node (ref "IC1") (pin "21") (pinfunction "GPA0_21") (pintype "bidirectional"))
      (node (ref "R1") (pin "1") (pinfunction "1_1") (pintype "passive"))
    )
    (net (code "67") (name "GPA0-2") (class "Default")
      (node (ref "IC2") (pin "21") (pinfunction "GPA0_21") (pintype "bidirectional"))
      (node (ref "R17") (pin "1") (pinfunction "1_1") (pintype "passive"))
    )
    (net (code "68") (name "GPA0-3") (class "Default")
      (node (ref "IC3") (pin "21") (pinfunction "GPA0_21") (pintype "bidirectional"))
      (node (ref "R33") (pin "1") (pinfunction "1_1") (pintype "passive"))
    )
    (net (code "69") (name "GPA0-4") (class "Default")
      (node (ref "IC4") (pin "21") (pinfunction "GPA0_21") (pintype "bidirectional"))
      (node (ref "R51") (pin "1") (pinfunction "1_1") (pintype "passive"))
    )
    (net (code "70") (name "GPA1-1") (class "Default")
      (node (ref "IC1") (pin "22") (pinfunction "GPA1_22") (pintype "bidirectional"))
      (node (ref "R3") (pin "1") (pinfunction "1_1") (pintype "passive"))
    )
    (net (code "71") (name "GPA1-2") (class "Default")
      (node (ref "IC2") (pin "22") (pinfunction "GPA1_22") (pintype "bidirectional"))
      (node (ref "R19") (pin "1") (pinfunction "1_1") (pintype "passive"))
    )
    (net (code "72") (name "GPA1-3") (class "Default")
      (node (ref "IC3") (pin "22") (pinfunction "GPA1_22") (pintype "bidirectional"))
      (node (ref "R35") (pin "1") (pinfunction "1_1") (pintype "passive"))
    )
    (net (code "73") (name "GPA1-4") (class "Default")
      (node (ref "IC4") (pin "22") (pinfunction "GPA1_22") (pintype "bidirectional"))
      (node (ref "R53") (pin "1") (pinfunction "1_1") (pintype "passive"))
    )
    (net (code "74") (name "GPA2-1") (class "Default")
      (node (ref "IC1") (pin "23") (pinfunction "GPA2_23") (pintype "bidirectional"))
      (node (ref "R2") (pin "1") (pinfunction "1_1") (pintype "passive"))
    )
    (net (code "75") (name "GPA2-2") (class "Default")
      (node (ref "IC2") (pin "23") (pinfunction "GPA2_23") (pintype "bidirectional"))
      (node (ref "R18") (pin "1") (pinfunction "1_1") (pintype "passive"))
    )
    (net (code "76") (name "GPA2-3") (class "Default")
      (node (ref "IC3") (pin "23") (pinfunction "GPA2_23") (pintype "bidirectional"))
      (node (ref "R34") (pin "1") (pinfunction "1_1") (pintype "passive"))
    )
    (net (code "77") (name "GPA2-4") (class "Default")
      (node (ref "IC4") (pin "23") (pinfunction "GPA2_23") (pintype "bidirectional"))
      (node (ref "R52") (pin "1") (pinfunction "1_1") (pintype "passive"))
    )
    (net (code "78") (name "GPA3-1") (class "Default")
      (node (ref "IC1") (pin "24") (pinfunction "GPA3_24") (pintype "bidirectional"))
      (node (ref "R4") (pin "1") (pinfunction "1_1") (pintype "passive"))
    )
    (net (code "79") (name "GPA3-2") (class "Default")
      (node (ref "IC2") (pin "24") (pinfunction "GPA3_24") (pintype "bidirectional"))
      (node (ref "R20") (pin "1") (pinfunction "1_1") (pintype "passive"))
    )
    (net (code "80") (name "GPA3-3") (class "Default")
      (node (ref "IC3") (pin "24") (pinfunction "GPA3_24") (pintype "bidirectional"))
      (node (ref "R36") (pin "1") (pinfunction "1_1") (pintype "passive"))
    )
    (net (code "81") (name "GPA3-4") (class "Default")
      (node (ref "IC4") (pin "24") (pinfunction "GPA3_24") (pintype "bidirectional"))
      (node (ref "R54") (pin "1") (pinfunction "1_1") (pintype "passive"))
    )
    (net (code "82") (name "GPA4-1") (class "Default")
      (node (ref "IC1") (pin "25") (pinfunction "GPA4_25") (pintype "bidirectional"))
      (node (ref "R7") (pin "1") (pinfunction "1_1") (pintype "passive"))
    )
    (net (code "83") (name "GPA4-2") (class "Default")
      (node (ref "IC2") (pin "25") (pinfunction "GPA4_25") (pintype "bidirectional"))
      (node (ref "R23") (pin "1") (pinfunction "1_1") (pintype "passive"))
    )
    (net (code "84") (name "GPA4-3") (class "Default")
      (node (ref "IC3") (pin "25") (pinfunction "GPA4_25") (pintype "bidirectional"))
      (node (ref "R41") (pin "1") (pinfunction "1_1") (pintype "passive"))
    )
    (net (code "85") (name "GPA4-4") (class "Default")
      (node (ref "IC4") (pin "25") (pinfunction "GPA4_25") (pintype "bidirectional"))
      (node (ref "R57") (pin "1") (pinfunction "1_1") (pintype "passive"))
    )
    (net (code "86") (name "GPA5-1") (class "Default")
      (node (ref "IC1") (pin "26") (pinfunction "GPA5_26") (pintype "bidirectional"))
      (node (ref "R6") (pin "1") (pinfunction "1_1") (pintype "passive"))
    )
    (net (code "87") (name "GPA5-2") (class "Default")
      (node (ref "IC2") (pin "26") (pinfunction "GPA5_26") (pintype "bidirectional"))
      (node (ref "R22") (pin "1") (pinfunction "1_1") (pintype "passive"))
    )
    (net (code "88") (name "GPA5-3") (class "Default")
      (node (ref "IC3") (pin "26") (pinfunction "GPA5_26") (pintype "bidirectional"))
      (node (ref "R38") (pin "1") (pinfunction "1_1") (pintype "passive"))
    )
    (net (code "89") (name "GPA5-4") (class "Default")
      (node (ref "IC4") (pin "26") (pinfunction "GPA5_26") (pintype "bidirectional"))
      (node (ref "R56") (pin "1") (pinfunction "1_1") (pintype "passive"))
    )
    (net (code "90") (name "GPA6-1") (class "Default")
      (node (ref "IC1") (pin "27") (pinfunction "GPA6_27") (pintype "bidirectional"))
      (node (ref "R5") (pin "1") (pinfunction "1_1") (pintype "passive"))
    )
    (net (code "91") (name "GPA6-2") (class "Default")
      (node (ref "IC2") (pin "27") (pinfunction "GPA6_27") (pintype "bidirectional"))
      (node (ref "R21") (pin "1") (pinfunction "1_1") (pintype "passive"))
    )
    (net (code "92") (name "GPA6-3") (class "Default")
      (node (ref "IC3") (pin "27") (pinfunction "GPA6_27") (pintype "bidirectional"))
      (node (ref "R37") (pin "1") (pinfunction "1_1") (pintype "passive"))
    )
    (net (code "93") (name "GPA6-4") (class "Default")
      (node (ref "IC4") (pin "27") (pinfunction "GPA6_27") (pintype "bidirectional"))
      (node (ref "R55") (pin "1") (pinfunction "1_1") (pintype "passive"))
    )
    (net (code "94") (name "GPA7-1") (class "Default")
      (node (ref "IC1") (pin "28") (pinfunction "GPA7_28") (pintype "bidirectional"))
      (node (ref "R8") (pin "1") (pinfunction "1_1") (pintype "passive"))
    )
    (net (code "95") (name "GPA7-2") (class "Default")
      (node (ref "IC2") (pin "28") (pinfunction "GPA7_28") (pintype "bidirectional"))
      (node (ref "R24") (pin "1") (pinfunction "1_1") (pintype "passive"))
    )
    (net (code "96") (name "GPA7-3") (class "Default")
      (node (ref "IC3") (pin "28") (pinfunction "GPA7_28") (pintype "bidirectional"))
      (node (ref "R42") (pin "1") (pinfunction "1_1") (pintype "passive"))
    )
    (net (code "97") (name "GPA7-4") (class "Default")
      (node (ref "IC4") (pin "28") (pinfunction "GPA7_28") (pintype "bidirectional"))
      (node (ref "R58") (pin "1") (pinfunction "1_1") (pintype "passive"))
    )
    (net (code "98") (name "GPB0-1") (class "Default")
      (node (ref "IC1") (pin "1") (pinfunction "GPB0_1") (pintype "bidirectional"))
      (node (ref "R15") (pin "1") (pinfunction "1_1") (pintype "passive"))
    )
    (net (code "99") (name "GPB0-2") (class "Default")
      (node (ref "IC2") (pin "1") (pinfunction "GPB0_1") (pintype "bidirectional"))
      (node (ref "R31") (pin "1") (pinfunction "1_1") (pintype "passive"))
    )
    (net (code "100") (name "GPB0-3") (class "Default")
      (node (ref "IC3") (pin "1") (pinfunction "GPB0_1") (pintype "bidirectional"))
      (node (ref "R49") (pin "1") (pinfunction "1_1") (pintype "passive"))
    )
    (net (code "101") (name "GPB0-4") (class "Default")
      (node (ref "IC4") (pin "1") (pinfunction "GPB0_1") (pintype "bidirectional"))
      (node (ref "R40") (pin "1") (pinfunction "1_1") (pintype "passive"))
    )
    (net (code "102") (name "GPB1-1") (class "Default")
      (node (ref "IC1") (pin "2") (pinfunction "GPB1_2") (pintype "bidirectional"))
      (node (ref "R13") (pin "1") (pinfunction "1_1") (pintype "passive"))
    )
    (net (code "103") (name "GPB1-2") (class "Default")
      (node (ref "IC2") (pin "2") (pinfunction "GPB1_2") (pintype "bidirectional"))
      (node (ref "R29") (pin "1") (pinfunction "1_1") (pintype "passive"))
    )
    (net (code "104") (name "GPB1-3") (class "Default")
      (node (ref "IC3") (pin "2") (pinfunction "GPB1_2") (pintype "bidirectional"))
      (node (ref "R47") (pin "1") (pinfunction "1_1") (pintype "passive"))
    )
    (net (code "105") (name "GPB1-4") (class "Default")
      (node (ref "IC4") (pin "2") (pinfunction "GPB1_2") (pintype "bidirectional"))
      (node (ref "R63") (pin "1") (pinfunction "1_1") (pintype "passive"))
    )
    (net (code "106") (name "GPB2-1") (class "Default")
      (node (ref "IC1") (pin "3") (pinfunction "GPB2_3") (pintype "bidirectional"))
      (node (ref "R11") (pin "1") (pinfunction "1_1") (pintype "passive"))
    )
    (net (code "107") (name "GPB2-2") (class "Default")
      (node (ref "IC2") (pin "3") (pinfunction "GPB2_3") (pintype "bidirectional"))
      (node (ref "R27") (pin "1") (pinfunction "1_1") (pintype "passive"))
    )
    (net (code "108") (name "GPB2-3") (class "Default")
      (node (ref "IC3") (pin "3") (pinfunction "GPB2_3") (pintype "bidirectional"))
      (node (ref "R45") (pin "1") (pinfunction "1_1") (pintype "passive"))
    )
    (net (code "109") (name "GPB2-4") (class "Default")
      (node (ref "IC4") (pin "3") (pinfunction "GPB2_3") (pintype "bidirectional"))
      (node (ref "R61") (pin "1") (pinfunction "1_1") (pintype "passive"))
    )
    (net (code "110") (name "GPB3-1") (class "Default")
      (node (ref "IC1") (pin "4") (pinfunction "GPB3_4") (pintype "bidirectional"))
      (node (ref "R9") (pin "1") (pinfunction "1_1") (pintype "passive"))
    )
    (net (code "111") (name "GPB3-2") (class "Default")
      (node (ref "IC2") (pin "4") (pinfunction "GPB3_4") (pintype "bidirectional"))
      (node (ref "R25") (pin "1") (pinfunction "1_1") (pintype "passive"))
    )
    (net (code "112") (name "GPB3-3") (class "Default")
      (node (ref "IC3") (pin "4") (pinfunction "GPB3_4") (pintype "bidirectional"))
      (node (ref "R43") (pin "1") (pinfunction "1_1") (pintype "passive"))
    )
    (net (code "113") (name "GPB3-4") (class "Default")
      (node (ref "IC4") (pin "4") (pinfunction "GPB3_4") (pintype "bidirectional"))
      (node (ref "R59") (pin "1") (pinfunction "1_1") (pintype "passive"))
    )
    (net (code "114") (name "GPB4-1") (class "Default")
      (node (ref "IC1") (pin "5") (pinfunction "GPB4_5") (pintype "bidirectional"))
      (node (ref "R16") (pin "1") (pinfunction "1_1") (pintype "passive"))
    )
    (net (code "115") (name "GPB4-2") (class "Default")
      (node (ref "IC2") (pin "5") (pinfunction "GPB4_5") (pintype "bidirectional"))
      (node (ref "R32") (pin "1") (pinfunction "1_1") (pintype "passive"))
    )
    (net (code "116") (name "GPB4-3") (class "Default")
      (node (ref "IC3") (pin "5") (pinfunction "GPB4_5") (pintype "bidirectional"))
      (node (ref "R50") (pin "1") (pinfunction "1_1") (pintype "passive"))
    )
    (net (code "117") (name "GPB4-4") (class "Default")
      (node (ref "IC4") (pin "5") (pinfunction "GPB4_5") (pintype "bidirectional"))
      (node (ref "R39") (pin "1") (pinfunction "1_1") (pintype "passive"))
    )
    (net (code "118") (name "GPB5-1") (class "Default")
      (node (ref "IC1") (pin "6") (pinfunction "GPB5_6") (pintype "bidirectional"))
      (node (ref "R14") (pin "1") (pinfunction "1_1") (pintype "passive"))
    )
    (net (code "119") (name "GPB5-2") (class "Default")
      (node (ref "IC2") (pin "6") (pinfunction "GPB5_6") (pintype "bidirectional"))
      (node (ref "R30") (pin "1") (pinfunction "1_1") (pintype "passive"))
    )
    (net (code "120") (name "GPB5-3") (class "Default")
      (node (ref "IC3") (pin "6") (pinfunction "GPB5_6") (pintype "bidirectional"))
      (node (ref "R48") (pin "1") (pinfunction "1_1") (pintype "passive"))
    )
    (net (code "121") (name "GPB5-4") (class "Default")
      (node (ref "IC4") (pin "6") (pinfunction "GPB5_6") (pintype "bidirectional"))
      (node (ref "R64") (pin "1") (pinfunction "1_1") (pintype "passive"))
    )
    (net (code "122") (name "GPB6-1") (class "Default")
      (node (ref "IC1") (pin "7") (pinfunction "GPB6_7") (pintype "bidirectional"))
      (node (ref "R12") (pin "1") (pinfunction "1_1") (pintype "passive"))
    )
    (net (code "123") (name "GPB6-2") (class "Default")
      (node (ref "IC2") (pin "7") (pinfunction "GPB6_7") (pintype "bidirectional"))
      (node (ref "R28") (pin "1") (pinfunction "1_1") (pintype "passive"))
    )
    (net (code "124") (name "GPB6-3") (class "Default")
      (node (ref "IC3") (pin "7") (pinfunction "GPB6_7") (pintype "bidirectional"))
      (node (ref "R46") (pin "1") (pinfunction "1_1") (pintype "passive"))
    )
    (net (code "125") (name "GPB6-4") (class "Default")
      (node (ref "IC4") (pin "7") (pinfunction "GPB6_7") (pintype "bidirectional"))
      (node (ref "R62") (pin "1") (pinfunction "1_1") (pintype "passive"))
    )
    (net (code "126") (name "GPB7-1") (class "Default")
      (node (ref "IC1") (pin "8") (pinfunction "GPB7_8") (pintype "bidirectional"))
      (node (ref "R10") (pin "1") (pinfunction "1_1") (pintype "passive"))
    )
    (net (code "127") (name "GPB7-2") (class "Default")
      (node (ref "IC2") (pin "8") (pinfunction "GPB7_8") (pintype "bidirectional"))
      (node (ref "R26") (pin "1") (pinfunction "1_1") (pintype "passive"))
    )
    (net (code "128") (name "GPB7-3") (class "Default")
      (node (ref "IC3") (pin "8") (pinfunction "GPB7_8") (pintype "bidirectional"))
      (node (ref "R44") (pin "1") (pinfunction "1_1") (pintype "passive"))
    )
    (net (code "129") (name "GPB7-4") (class "Default")
      (node (ref "IC4") (pin "8") (pinfunction "GPB7_8") (pintype "bidirectional"))
      (node (ref "R60") (pin "1") (pinfunction "1_1") (pintype "passive"))
    )
    (net (code "130") (name "Net-(LED1-PadA)") (class "Default")
      (node (ref "LED1") (pin "A") (pinfunction "A_A") (pintype "passive"))
      (node (ref "R66") (pin "1") (pinfunction "1_1") (pintype "passive"))
    )
    (net (code "131") (name "Net-(LED2-PadA)") (class "Default")
      (node (ref "LED2") (pin "A") (pinfunction "A_A") (pintype "passive"))
      (node (ref "R65") (pin "1") (pinfunction "1_1") (pintype "passive"))
    )
    (net (code "132") (name "Net-(R67-Pad2)") (class "Default")
      (node (ref "R67") (pin "2") (pinfunction "2_2") (pintype "passive"))
      (node (ref "SJ2") (pin "1") (pinfunction "1_1") (pintype "passive"))
    )
    (net (code "133") (name "Net-(R68-Pad2)") (class "Default")
      (node (ref "R68") (pin "2") (pinfunction "2_2") (pintype "passive"))
      (node (ref "SJ1") (pin "1") (pinfunction "1_1") (pintype "passive"))
    )
    (net (code "134") (name "Net-(R69-Pad2)") (class "Default")
      (node (ref "R69") (pin "2") (pinfunction "2_2") (pintype "passive"))
      (node (ref "SJ3") (pin "1") (pinfunction "1_1") (pintype "passive"))
    )
    (net (code "135") (name "SCL") (class "Default")
      (node (ref "IC1") (pin "12") (pinfunction "SCL_12") (pintype "input"))
      (node (ref "IC2") (pin "12") (pinfunction "SCL_12") (pintype "input"))
      (node (ref "IC3") (pin "12") (pinfunction "SCL_12") (pintype "input"))
      (node (ref "IC4") (pin "12") (pinfunction "SCL_12") (pintype "input"))
      (node (ref "J1") (pin "1") (pinfunction "1_1") (pintype "passive"))
      (node (ref "J2") (pin "1") (pinfunction "1_1") (pintype "passive"))
      (node (ref "R67") (pin "1") (pinfunction "1_1") (pintype "passive"))
    )
    (net (code "136") (name "SDA") (class "Default")
      (node (ref "IC1") (pin "13") (pinfunction "SDA_13") (pintype "bidirectional"))
      (node (ref "IC2") (pin "13") (pinfunction "SDA_13") (pintype "bidirectional"))
      (node (ref "IC3") (pin "13") (pinfunction "SDA_13") (pintype "bidirectional"))
      (node (ref "IC4") (pin "13") (pinfunction "SDA_13") (pintype "bidirectional"))
      (node (ref "J1") (pin "2") (pinfunction "2_2") (pintype "passive"))
      (node (ref "J2") (pin "2") (pinfunction "2_2") (pintype "passive"))
      (node (ref "R68") (pin "1") (pinfunction "1_1") (pintype "passive"))
    )
    (net (code "137") (name "VCC") (class "Default")
      (node (ref "C1") (pin "1") (pinfunction "1_1") (pintype "passive"))
      (node (ref "C2") (pin "1") (pinfunction "1_1") (pintype "passive"))
      (node (ref "C3") (pin "1") (pinfunction "1_1") (pintype "passive"))
      (node (ref "C4") (pin "1") (pinfunction "1_1") (pintype "passive"))
      (node (ref "IC1") (pin "9") (pinfunction "VDD_9") (pintype "power_in"))
      (node (ref "IC2") (pin "15") (pinfunction "A0_15") (pintype "input"))
      (node (ref "IC2") (pin "9") (pinfunction "VDD_9") (pintype "power_in"))
      (node (ref "IC3") (pin "16") (pinfunction "A1_16") (pintype "input"))
      (node (ref "IC3") (pin "9") (pinfunction "VDD_9") (pintype "power_in"))
      (node (ref "IC4") (pin "15") (pinfunction "A0_15") (pintype "input"))
      (node (ref "IC4") (pin "16") (pinfunction "A1_16") (pintype "input"))
      (node (ref "IC4") (pin "9") (pinfunction "VDD_9") (pintype "power_in"))
      (node (ref "J1") (pin "5") (pinfunction "5_5") (pintype "passive"))
      (node (ref "J2") (pin "5") (pinfunction "5_5") (pintype "passive"))
      (node (ref "R65") (pin "2") (pinfunction "2_2") (pintype "passive"))
      (node (ref "SJ1") (pin "2") (pinfunction "2_2") (pintype "passive"))
      (node (ref "SJ2") (pin "2") (pinfunction "2_2") (pintype "passive"))
      (node (ref "SJ3") (pin "2") (pinfunction "2_2") (pintype "passive"))
    )
    (net (code "138") (name "VIN") (class "Default")
      (node (ref "C5") (pin "+") (pinfunction "+_+") (pintype "passive"))
      (node (ref "J1") (pin "3") (pinfunction "3_3") (pintype "passive"))
      (node (ref "J2") (pin "3") (pinfunction "3_3") (pintype "passive"))
      (node (ref "J4") (pin "A4") (pinfunction "A4_A4") (pintype "bidirectional"))
      (node (ref "J4") (pin "A5") (pinfunction "A5_A5") (pintype "bidirectional"))
      (node (ref "J4") (pin "B4") (pinfunction "B4_B4") (pintype "bidirectional"))
      (node (ref "J4") (pin "B5") (pinfunction "B5_B5") (pintype "bidirectional"))
      (node (ref "J4") (pin "C4") (pinfunction "C4_C4") (pintype "bidirectional"))
      (node (ref "J4") (pin "C5") (pinfunction "C5_C5") (pintype "bidirectional"))
      (node (ref "J4") (pin "D4") (pinfunction "D4_D4") (pintype "bidirectional"))
      (node (ref "J4") (pin "D5") (pinfunction "D5_D5") (pintype "bidirectional"))
      (node (ref "J4") (pin "E4") (pinfunction "E4_E4") (pintype "bidirectional"))
      (node (ref "J4") (pin "E5") (pinfunction "E5_E5") (pintype "bidirectional"))
      (node (ref "J4") (pin "F4") (pinfunction "F4_F4") (pintype "bidirectional"))
      (node (ref "J4") (pin "F5") (pinfunction "F5_F5") (pintype "bidirectional"))
      (node (ref "J4") (pin "G4") (pinfunction "G4_G4") (pintype "bidirectional"))
      (node (ref "J4") (pin "G5") (pinfunction "G5_G5") (pintype "bidirectional"))
      (node (ref "J4") (pin "H4") (pinfunction "H4_H4") (pintype "bidirectional"))
      (node (ref "J4") (pin "H5") (pinfunction "H5_H5") (pintype "bidirectional"))
      (node (ref "J5") (pin "A4") (pinfunction "A4_A4") (pintype "bidirectional"))
      (node (ref "J5") (pin "A5") (pinfunction "A5_A5") (pintype "bidirectional"))
      (node (ref "J5") (pin "B4") (pinfunction "B4_B4") (pintype "bidirectional"))
      (node (ref "J5") (pin "B5") (pinfunction "B5_B5") (pintype "bidirectional"))
      (node (ref "J5") (pin "C4") (pinfunction "C4_C4") (pintype "bidirectional"))
      (node (ref "J5") (pin "C5") (pinfunction "C5_C5") (pintype "bidirectional"))
      (node (ref "J5") (pin "D4") (pinfunction "D4_D4") (pintype "bidirectional"))
      (node (ref "J5") (pin "D5") (pinfunction "D5_D5") (pintype "bidirectional"))
      (node (ref "J5") (pin "E4") (pinfunction "E4_E4") (pintype "bidirectional"))
      (node (ref "J5") (pin "E5") (pinfunction "E5_E5") (pintype "bidirectional"))
      (node (ref "J5") (pin "F4") (pinfunction "F4_F4") (pintype "bidirectional"))
      (node (ref "J5") (pin "F5") (pinfunction "F5_F5") (pintype "bidirectional"))
      (node (ref "J5") (pin "G4") (pinfunction "G4_G4") (pintype "bidirectional"))
      (node (ref "J5") (pin "G5") (pinfunction "G5_G5") (pintype "bidirectional"))
      (node (ref "J5") (pin "H4") (pinfunction "H4_H4") (pintype "bidirectional"))
      (node (ref "J5") (pin "H5") (pinfunction "H5_H5") (pintype "bidirectional"))
      (node (ref "R66") (pin "2") (pinfunction "2_2") (pintype "passive"))
    )
    (net (code "139") (name "unconnected-(IC1-INTB-Pad19)") (class "Default")
      (node (ref "IC1") (pin "19") (pinfunction "INTB_19") (pintype "output"))
    )
    (net (code "140") (name "unconnected-(IC2-INTB-Pad19)") (class "Default")
      (node (ref "IC2") (pin "19") (pinfunction "INTB_19") (pintype "output"))
    )
    (net (code "141") (name "unconnected-(IC3-INTB-Pad19)") (class "Default")
      (node (ref "IC3") (pin "19") (pinfunction "INTB_19") (pintype "output"))
    )
    (net (code "142") (name "unconnected-(IC4-INTB-Pad19)") (class "Default")
      (node (ref "IC4") (pin "19") (pinfunction "INTB_19") (pintype "output"))
    )
    (net (code "143") (name "~{INT}") (class "Default")
      (node (ref "IC1") (pin "20") (pinfunction "INTA_20") (pintype "output"))
      (node (ref "IC2") (pin "20") (pinfunction "INTA_20") (pintype "output"))
      (node (ref "IC3") (pin "20") (pinfunction "INTA_20") (pintype "output"))
      (node (ref "IC4") (pin "20") (pinfunction "INTA_20") (pintype "output"))
      (node (ref "J3") (pin "1") (pinfunction "1_1") (pintype "passive"))
    )
    (net (code "144") (name "~{RESET}") (class "Default")
      (node (ref "IC1") (pin "18") (pinfunction "~{RESET}_18") (pintype "input"))
      (node (ref "IC2") (pin "18") (pinfunction "~{RESET}_18") (pintype "input"))
      (node (ref "IC3") (pin "18") (pinfunction "~{RESET}_18") (pintype "input"))
      (node (ref "IC4") (pin "18") (pinfunction "~{RESET}_18") (pintype "input"))
      (node (ref "J1") (pin "6") (pinfunction "6_6") (pintype "passive"))
      (node (ref "J2") (pin "6") (pinfunction "6_6") (pintype "passive"))
      (node (ref "R69") (pin "1") (pinfunction "1_1") (pintype "passive"))
    )
  )
)
